# Christmas_Kit.net
KiCad netlist of a schematic drawn in EAGLE
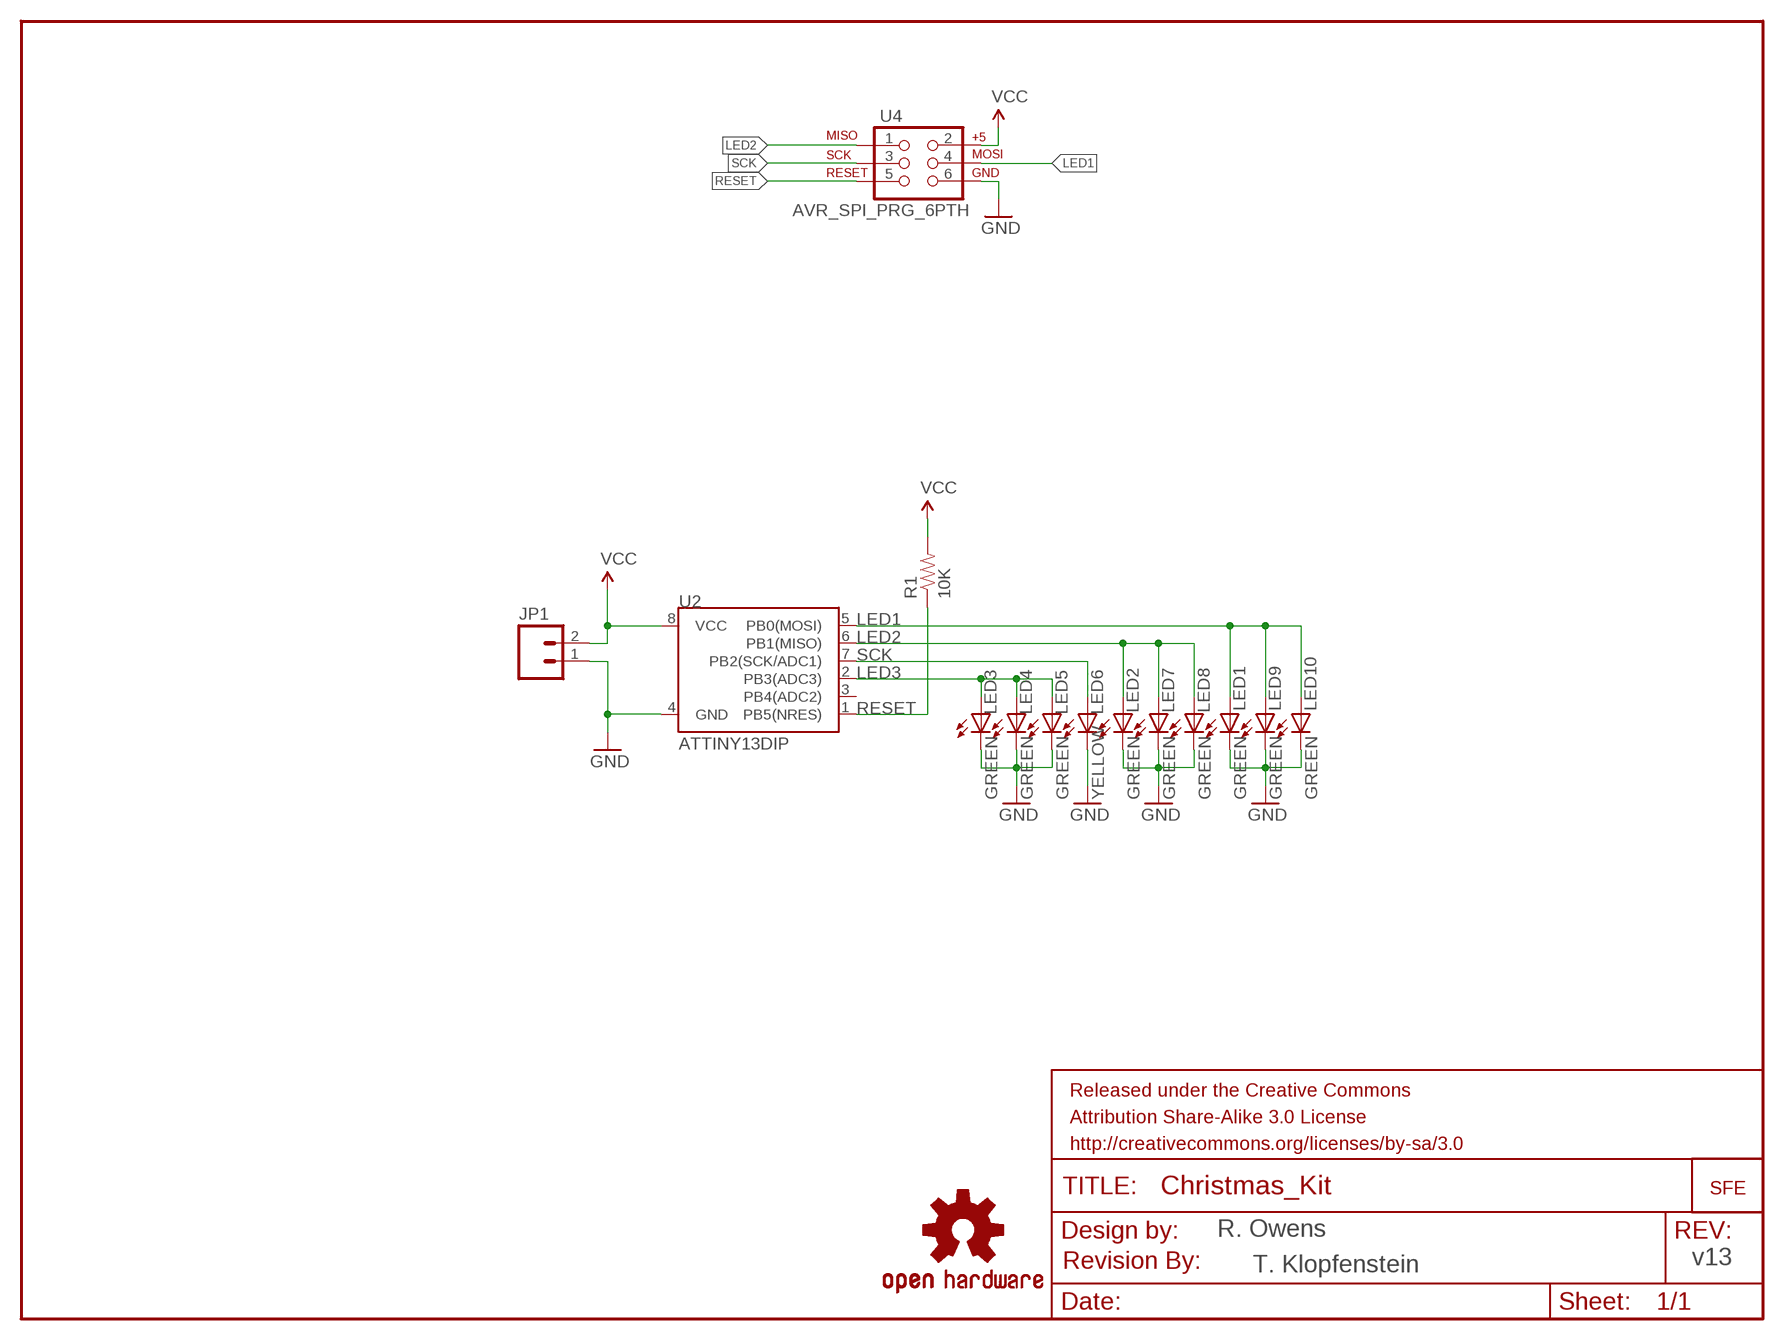
[diagram p0: schematic, sheet 1]

(export (version "E")
  (design (tool "Eeschema 10.0.6"))
  (components
    (comp (ref "FRAME1")
      (value "FRAME-LETTER")
      (footprint "eagle-import:CREATIVE_COMMONS")
      (libsource (lib "eagle-import") (part "FRAME-LETTER"))
    )
    (comp (ref "JP1")
      (value "M02PTH")
      (footprint "eagle-import:1X02")
      (libsource (lib "eagle-import") (part "M02PTH"))
    )
    (comp (ref "JP2")
      (value "LOGO-SFENEW")
      (footprint "eagle-import:SFE-NEW-WEBLOGO")
      (libsource (lib "eagle-import") (part "LOGO-SFENEW"))
    )
    (comp (ref "LED1")
      (value "GREEN")
      (footprint "eagle-import:LED5MM")
      (libsource (lib "eagle-import") (part "LED5MM"))
    )
    (comp (ref "LED2")
      (value "GREEN")
      (footprint "eagle-import:LED5MM")
      (libsource (lib "eagle-import") (part "LED5MM"))
    )
    (comp (ref "LED3")
      (value "GREEN")
      (footprint "eagle-import:LED5MM")
      (libsource (lib "eagle-import") (part "LED5MM"))
    )
    (comp (ref "LED4")
      (value "GREEN")
      (footprint "eagle-import:LED5MM")
      (libsource (lib "eagle-import") (part "LED5MM"))
    )
    (comp (ref "LED5")
      (value "GREEN")
      (footprint "eagle-import:LED5MM")
      (libsource (lib "eagle-import") (part "LED5MM"))
    )
    (comp (ref "LED6")
      (value "YELLOW")
      (footprint "eagle-import:LED3MM")
      (libsource (lib "eagle-import") (part "LED3MM"))
    )
    (comp (ref "LED7")
      (value "GREEN")
      (footprint "eagle-import:LED5MM")
      (libsource (lib "eagle-import") (part "LED5MM"))
    )
    (comp (ref "LED8")
      (value "GREEN")
      (footprint "eagle-import:LED5MM")
      (libsource (lib "eagle-import") (part "LED5MM"))
    )
    (comp (ref "LED9")
      (value "GREEN")
      (footprint "eagle-import:LED5MM")
      (libsource (lib "eagle-import") (part "LED5MM"))
    )
    (comp (ref "LED10")
      (value "GREEN")
      (footprint "eagle-import:LED5MM")
      (libsource (lib "eagle-import") (part "LED5MM"))
    )
    (comp (ref "LOGO1")
      (value "OSHW-LOGOL")
      (footprint "eagle-import:OSHW-LOGO-L")
      (libsource (lib "eagle-import") (part "OSHW-LOGOL"))
    )
    (comp (ref "R1")
      (value "10K")
      (footprint "eagle-import:AXIAL-0.3")
      (libsource (lib "eagle-import") (part "RESISTORPTH1"))
    )
    (comp (ref "U$1")
      (value "REVISION")
      (footprint "eagle-import:REVISION")
      (libsource (lib "eagle-import") (part "REVISION"))
    )
    (comp (ref "U2")
      (value "ATTINY13DIP")
      (footprint "eagle-import:DIP08")
      (libsource (lib "eagle-import") (part "ATTINY13DIP"))
    )
    (comp (ref "U4")
      (value "AVR_SPI_PRG_6PTH")
      (footprint "eagle-import:2X3")
      (libsource (lib "eagle-import") (part "AVR_SPI_PRG_6PTH"))
    )
  )
  (nets
    (net (code "1") (name "/LED3") (class "Default")
      (node (ref "LED3") (pin "A") (pinfunction "A_A") (pintype "passive"))
      (node (ref "LED4") (pin "A") (pinfunction "A_A") (pintype "passive"))
      (node (ref "LED5") (pin "A") (pinfunction "A_A") (pintype "passive"))
      (node (ref "U2") (pin "2") (pinfunction "PB3(ADC3)_2") (pintype "bidirectional"))
    )
    (net (code "2") (name "GND") (class "Default")
      (node (ref "JP1") (pin "1") (pinfunction "1_1") (pintype "passive"))
      (node (ref "LED1") (pin "K") (pinfunction "C_K") (pintype "passive"))
      (node (ref "LED10") (pin "K") (pinfunction "C_K") (pintype "passive"))
      (node (ref "LED2") (pin "K") (pinfunction "C_K") (pintype "passive"))
      (node (ref "LED3") (pin "K") (pinfunction "C_K") (pintype "passive"))
      (node (ref "LED4") (pin "K") (pinfunction "C_K") (pintype "passive"))
      (node (ref "LED5") (pin "K") (pinfunction "C_K") (pintype "passive"))
      (node (ref "LED6") (pin "K") (pinfunction "C_K") (pintype "passive"))
      (node (ref "LED7") (pin "K") (pinfunction "C_K") (pintype "passive"))
      (node (ref "LED8") (pin "K") (pinfunction "C_K") (pintype "passive"))
      (node (ref "LED9") (pin "K") (pinfunction "C_K") (pintype "passive"))
      (node (ref "U2") (pin "4") (pinfunction "GND_4") (pintype "bidirectional"))
      (node (ref "U4") (pin "6") (pinfunction "6_6") (pintype "passive"))
    )
    (net (code "3") (name "LED1") (class "Default")
      (node (ref "LED1") (pin "A") (pinfunction "A_A") (pintype "passive"))
      (node (ref "LED10") (pin "A") (pinfunction "A_A") (pintype "passive"))
      (node (ref "LED9") (pin "A") (pinfunction "A_A") (pintype "passive"))
      (node (ref "U2") (pin "5") (pinfunction "PB0(MOSI)_5") (pintype "bidirectional"))
      (node (ref "U4") (pin "4") (pinfunction "4_4") (pintype "passive"))
    )
    (net (code "4") (name "LED2") (class "Default")
      (node (ref "LED2") (pin "A") (pinfunction "A_A") (pintype "passive"))
      (node (ref "LED7") (pin "A") (pinfunction "A_A") (pintype "passive"))
      (node (ref "LED8") (pin "A") (pinfunction "A_A") (pintype "passive"))
      (node (ref "U2") (pin "6") (pinfunction "PB1(MISO)_6") (pintype "bidirectional"))
      (node (ref "U4") (pin "1") (pinfunction "1_1") (pintype "passive"))
    )
    (net (code "5") (name "RESET") (class "Default")
      (node (ref "R1") (pin "P$1") (pinfunction "1_P$1") (pintype "passive"))
      (node (ref "U2") (pin "1") (pinfunction "PB5(NRES)_1") (pintype "bidirectional"))
      (node (ref "U4") (pin "5") (pinfunction "5_5") (pintype "passive"))
    )
    (net (code "6") (name "SCK") (class "Default")
      (node (ref "LED6") (pin "A") (pinfunction "A_A") (pintype "passive"))
      (node (ref "U2") (pin "7") (pinfunction "PB2(SCK/ADC1)_7") (pintype "bidirectional"))
      (node (ref "U4") (pin "3") (pinfunction "3_3") (pintype "passive"))
    )
    (net (code "7") (name "VCC") (class "Default")
      (node (ref "JP1") (pin "2") (pinfunction "2_2") (pintype "passive"))
      (node (ref "R1") (pin "P$2") (pinfunction "2_P$2") (pintype "passive"))
      (node (ref "U2") (pin "8") (pinfunction "VCC_8") (pintype "bidirectional"))
      (node (ref "U4") (pin "2") (pinfunction "2_2") (pintype "passive"))
    )
    (net (code "8") (name "unconnected-(U2-PB4(ADC2)-Pad3)") (class "Default")
      (node (ref "U2") (pin "3") (pinfunction "PB4(ADC2)_3") (pintype "bidirectional"))
    )
  )
)
